# pceigr_v0_7.net
KiCad netlist of a schematic drawn in EAGLE
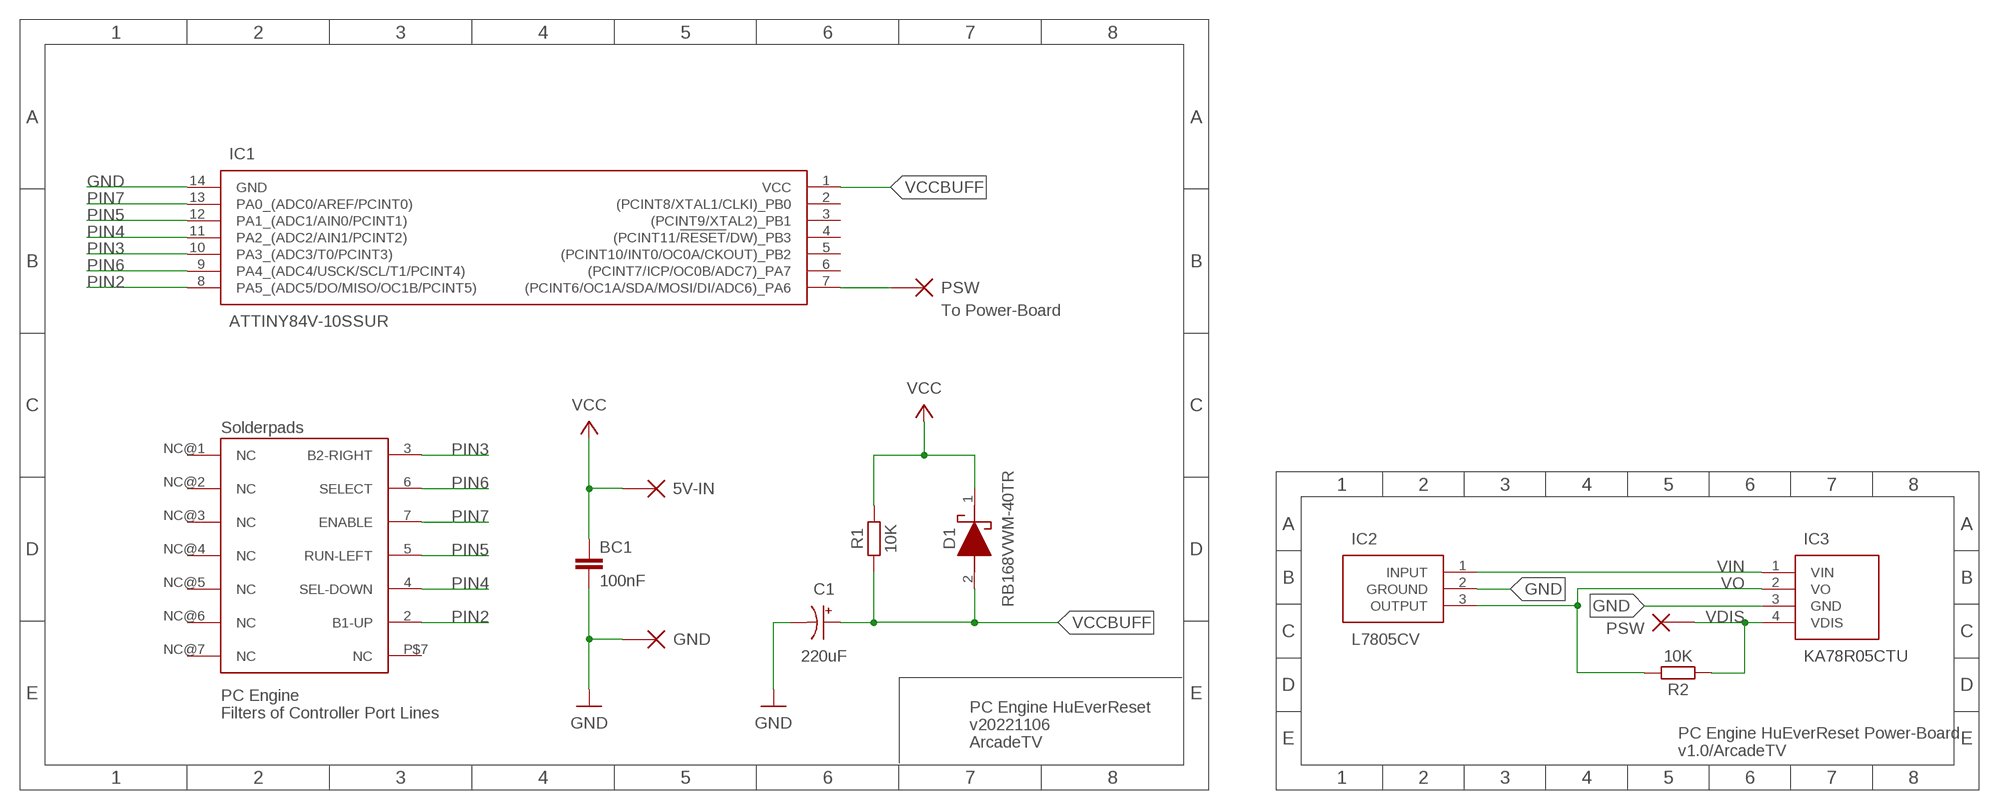
[diagram p0: schematic, sheet 1]

(export (version "E")
  (design (tool "Eeschema 10.0.6"))
  (components
    (comp (ref "BC1")
      (value "100nF")
      (footprint "eagle-import:Z0805")
      (libsource (lib "eagle-import") (part "C0805"))
    )
    (comp (ref "C1")
      (value "220uF")
      (footprint "eagle-import:C_6032-28R")
      (libsource (lib "eagle-import") (part "CPOL-USC/6032-28R"))
    )
    (comp (ref "D1")
      (value "RB168VWM-40TR")
      (footprint "eagle-import:RB168VWM40TR")
      (libsource (lib "eagle-import") (part "RB168VWM-40TR"))
    )
    (comp (ref "IC1")
      (value "ATTINY84V-10SSUR")
      (footprint "eagle-import:SOIC127P600X175-14N")
      (fields (field (name "MOUSER_PART_NUMBER") "556-ATTINY84V-10SSUR"))
      (libsource (lib "eagle-import") (part "ATTINY84V-10SSUR"))
    )
    (comp (ref "IC2")
      (value "L7805CV")
      (footprint "eagle-import:TO255P460X1020X2008-3P")
      (fields (field (name "MOUSER_PART_NUMBER") "511-L7805CV"))
      (libsource (lib "eagle-import") (part "L7805CV"))
    )
    (comp (ref "IC3")
      (value "KA78R05CTU")
      (footprint "eagle-import:PADS")
      (libsource (lib "eagle-import") (part "KA78R05CTUVERTICALMOUNT"))
    )
    (comp (ref "P1")
      (value "5V-IN")
      (footprint "eagle-import:PADS")
      (libsource (lib "eagle-import") (part "PAD"))
    )
    (comp (ref "P2")
      (value "GND")
      (footprint "eagle-import:PADS")
      (libsource (lib "eagle-import") (part "PAD"))
    )
    (comp (ref "P3")
      (value "PSW")
      (footprint "eagle-import:PADS")
      (libsource (lib "eagle-import") (part "PAD"))
    )
    (comp (ref "R1")
      (value "10K")
      (footprint "eagle-import:Z0805")
      (libsource (lib "eagle-import") (part "R0805"))
    )
    (comp (ref "R2")
      (value "10K")
      (footprint "eagle-import:Z0805")
      (libsource (lib "eagle-import") (part "R0805"))
    )
    (comp (ref "U$1")
      (value "PCE-CNTRL-FILTERS")
      (footprint "eagle-import:PCE-CNTRL-FILTERS")
      (libsource (lib "eagle-import") (part "PCE-CNTRL-FILTERS"))
    )
    (comp (ref "U$2")
      (value "PSW")
      (footprint "eagle-import:PADS")
      (libsource (lib "eagle-import") (part "PAD"))
    )
  )
  (nets
    (net (code "1") (name "/PIN2") (class "Default")
      (node (ref "IC1") (pin "8") (pinfunction "PA5_(ADC5/DO/MISO/OC1B/PCINT5)_8") (pintype "bidirectional"))
      (node (ref "U$1") (pin "2") (pinfunction "B1-UP_2") (pintype "bidirectional"))
    )
    (net (code "2") (name "/PIN3") (class "Default")
      (node (ref "IC1") (pin "10") (pinfunction "PA3_(ADC3/T0/PCINT3)_10") (pintype "bidirectional"))
      (node (ref "U$1") (pin "3") (pinfunction "B2-RIGHT_3") (pintype "bidirectional"))
    )
    (net (code "3") (name "/PIN4") (class "Default")
      (node (ref "IC1") (pin "11") (pinfunction "PA2_(ADC2/AIN1/PCINT2)_11") (pintype "bidirectional"))
      (node (ref "U$1") (pin "4") (pinfunction "SEL-DOWN_4") (pintype "bidirectional"))
    )
    (net (code "4") (name "/PIN5") (class "Default")
      (node (ref "IC1") (pin "12") (pinfunction "PA1_(ADC1/AIN0/PCINT1)_12") (pintype "bidirectional"))
      (node (ref "U$1") (pin "5") (pinfunction "RUN-LEFT_5") (pintype "bidirectional"))
    )
    (net (code "5") (name "/PIN6") (class "Default")
      (node (ref "IC1") (pin "9") (pinfunction "PA4_(ADC4/USCK/SCL/T1/PCINT4)_9") (pintype "bidirectional"))
      (node (ref "U$1") (pin "6") (pinfunction "SELECT_6") (pintype "bidirectional"))
    )
    (net (code "6") (name "/PIN7") (class "Default")
      (node (ref "IC1") (pin "13") (pinfunction "PA0_(ADC0/AREF/PCINT0)_13") (pintype "bidirectional"))
      (node (ref "U$1") (pin "7") (pinfunction "ENABLE_7") (pintype "bidirectional"))
    )
    (net (code "7") (name "/VDIS") (class "Default")
      (node (ref "IC3") (pin "4") (pinfunction "VDIS_4") (pintype "bidirectional"))
      (node (ref "R2") (pin "1") (pinfunction "1_1") (pintype "passive"))
      (node (ref "U$2") (pin "P$1") (pinfunction "P$1_P$1") (pintype "bidirectional"))
    )
    (net (code "8") (name "/VIN") (class "Default")
      (node (ref "IC2") (pin "1") (pinfunction "INPUT_1") (pintype "bidirectional"))
      (node (ref "IC3") (pin "1") (pinfunction "VIN_1") (pintype "input"))
    )
    (net (code "9") (name "/VO") (class "Default")
      (node (ref "IC2") (pin "3") (pinfunction "OUTPUT_3") (pintype "bidirectional"))
      (node (ref "IC3") (pin "2") (pinfunction "VO_2") (pintype "output"))
      (node (ref "R2") (pin "2") (pinfunction "2_2") (pintype "passive"))
    )
    (net (code "10") (name "GND") (class "Default")
      (node (ref "BC1") (pin "2") (pinfunction "2_2") (pintype "passive"))
      (node (ref "C1") (pin "-") (pinfunction "-_-") (pintype "passive"))
      (node (ref "IC1") (pin "14") (pinfunction "GND_14") (pintype "bidirectional"))
      (node (ref "IC2") (pin "2") (pinfunction "GROUND_2") (pintype "bidirectional"))
      (node (ref "IC3") (pin "3") (pinfunction "GND_3") (pintype "power_in"))
      (node (ref "P2") (pin "P$1") (pinfunction "P$1_P$1") (pintype "bidirectional"))
    )
    (net (code "11") (name "Net-(IC1-(PCINT6{slash}OC1A{slash}SDA{slash}MOSI{slash}DI{slash}ADC6)_PA6)") (class "Default")
      (node (ref "IC1") (pin "7") (pinfunction "(PCINT6/OC1A/SDA/MOSI/DI/ADC6)_PA6_7") (pintype "bidirectional"))
      (node (ref "P3") (pin "P$1") (pinfunction "P$1_P$1") (pintype "bidirectional"))
    )
    (net (code "12") (name "VCC") (class "Default")
      (node (ref "BC1") (pin "1") (pinfunction "1_1") (pintype "passive"))
      (node (ref "D1") (pin "1") (pinfunction "K_1") (pintype "bidirectional"))
      (node (ref "P1") (pin "P$1") (pinfunction "P$1_P$1") (pintype "bidirectional"))
      (node (ref "R1") (pin "2") (pinfunction "2_2") (pintype "passive"))
    )
    (net (code "13") (name "VCCBUFF") (class "Default")
      (node (ref "C1") (pin "+") (pinfunction "+_+") (pintype "passive"))
      (node (ref "D1") (pin "2") (pinfunction "A_2") (pintype "bidirectional"))
      (node (ref "IC1") (pin "1") (pinfunction "VCC_1") (pintype "bidirectional"))
      (node (ref "R1") (pin "1") (pinfunction "1_1") (pintype "passive"))
    )
    (net (code "14") (name "unconnected-(IC1-(PCINT7{slash}ICP{slash}OC0B{slash}ADC7)_PA7-Pad6)") (class "Default")
      (node (ref "IC1") (pin "6") (pinfunction "(PCINT7/ICP/OC0B/ADC7)_PA7_6") (pintype "bidirectional"))
    )
    (net (code "15") (name "unconnected-(IC1-(PCINT8{slash}XTAL1{slash}CLKI)_PB0-Pad2)") (class "Default")
      (node (ref "IC1") (pin "2") (pinfunction "(PCINT8/XTAL1/CLKI)_PB0_2") (pintype "bidirectional"))
    )
    (net (code "16") (name "unconnected-(IC1-(PCINT9{slash}XTAL2)_PB1-Pad3)") (class "Default")
      (node (ref "IC1") (pin "3") (pinfunction "(PCINT9/XTAL2)_PB1_3") (pintype "bidirectional"))
    )
    (net (code "17") (name "unconnected-(IC1-(PCINT10{slash}INT0{slash}OC0A{slash}CKOUT)_PB2-Pad5)") (class "Default")
      (node (ref "IC1") (pin "5") (pinfunction "(PCINT10/INT0/OC0A/CKOUT)_PB2_5") (pintype "bidirectional"))
    )
    (net (code "18") (name "unconnected-(IC1-(PCINT11{slash}~{RESET}{slash}DW)_PB3-Pad4)") (class "Default")
      (node (ref "IC1") (pin "4") (pinfunction "(PCINT11/~{RESET}/DW)_PB3_4") (pintype "bidirectional"))
    )
    (net (code "19") (name "unconnected-(U$1-NC-PadNC@1)") (class "Default")
      (node (ref "U$1") (pin "NC@1") (pinfunction "NC_NC@1") (pintype "bidirectional"))
    )
    (net (code "20") (name "unconnected-(U$1-NC-PadNC@2)") (class "Default")
      (node (ref "U$1") (pin "NC@2") (pinfunction "NC_NC@2") (pintype "bidirectional"))
    )
    (net (code "21") (name "unconnected-(U$1-NC-PadNC@3)") (class "Default")
      (node (ref "U$1") (pin "NC@3") (pinfunction "NC_NC@3") (pintype "bidirectional"))
    )
    (net (code "22") (name "unconnected-(U$1-NC-PadNC@4)") (class "Default")
      (node (ref "U$1") (pin "NC@4") (pinfunction "NC_NC@4") (pintype "bidirectional"))
    )
    (net (code "23") (name "unconnected-(U$1-NC-PadNC@5)") (class "Default")
      (node (ref "U$1") (pin "NC@5") (pinfunction "NC_NC@5") (pintype "bidirectional"))
    )
    (net (code "24") (name "unconnected-(U$1-NC-PadNC@6)") (class "Default")
      (node (ref "U$1") (pin "NC@6") (pinfunction "NC_NC@6") (pintype "bidirectional"))
    )
    (net (code "25") (name "unconnected-(U$1-NC-PadNC@7)") (class "Default")
      (node (ref "U$1") (pin "NC@7") (pinfunction "NC_NC@7") (pintype "bidirectional"))
    )
    (net (code "26") (name "unconnected-(U$1-NC-PadP$7)") (class "Default")
      (node (ref "U$1") (pin "P$7") (pinfunction "NC_P$7") (pintype "bidirectional"))
    )
  )
)
